# USB.net
KiCad netlist of a schematic drawn in Altium Designer
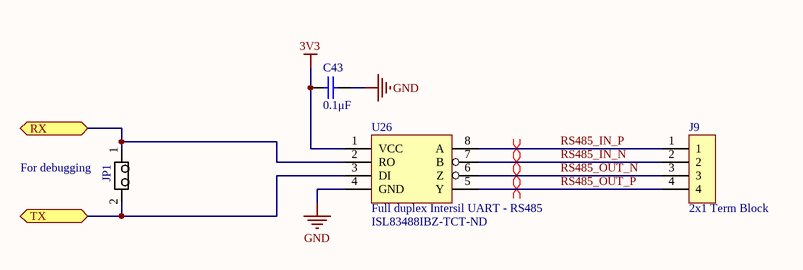
[diagram p0: USB.SchDoc]

(export (version "E")
  (design (tool "Eeschema 10.0.6"))
  (components
    (comp (ref "C43")
      (value "0.1μF")
      (footprint "CAPC1608N(0603\")")
      (description "Capacitor, Ceramic, 100V, +/- 10%, 0603 SMD, X7R")
      (fields
        (field (name "MFG") "TDK")
        (field (name "PUBLISHER") "AUVic")
        (field (name "CREATED BY") "Ashwin Sira")
      )
      (libsource (lib "AUVic_Integrated_Library_Capacitors") (part "0.1uF 100V 0603 SMD, Ceramic"))
    )
    (comp (ref "J9")
      (value "2x1 Term Block")
      (footprint "4X1 Terminal Block")
      (fields (field (name "MADE BY") "Andy Bates"))
      (libsource (lib "AUVic_Integrated_Library_Connectors") (part "4x1 Terminal Block"))
    )
    (comp (ref "JP1")
      (value "1X2 Pin Head")
      (footprint "2X1 Males Header")
      (fields (field (name "MADE BY") "Andy Bates"))
      (libsource (lib "AUVic_Schematic_Library_Connectors") (part "1x2 Male Header"))
    )
    (comp (ref "U26")
      (value "Full duplex Intersil UART - RS485")
      (footprint "SOIC-SN8_M")
      (fields
        (field (name "SUPPLIER PART NUMBER 1") "ISL83488IBZ-TCT-ND")
        (field (name "MADE BY") "Andy Bates")
      )
      (libsource (lib "AUVic_Integrated_Library_Interface") (part "Full duplex Intersil UART - RS485"))
    )
  )
  (nets
    (net (code "1") (name "/RS485_IN_N") (class "Default")
      (node (ref "J9") (pin "2") (pinfunction "2_2") (pintype "passive"))
      (node (ref "U26") (pin "7") (pinfunction "B_7") (pintype "passive"))
    )
    (net (code "2") (name "/RS485_IN_P") (class "Default")
      (node (ref "J9") (pin "1") (pinfunction "1_1") (pintype "passive"))
      (node (ref "U26") (pin "8") (pinfunction "A_8") (pintype "passive"))
    )
    (net (code "3") (name "/RS485_OUT_N") (class "Default")
      (node (ref "J9") (pin "3") (pinfunction "3_3") (pintype "passive"))
      (node (ref "U26") (pin "6") (pinfunction "Z_6") (pintype "passive"))
    )
    (net (code "4") (name "/RS485_OUT_P") (class "Default")
      (node (ref "J9") (pin "4") (pinfunction "4_4") (pintype "passive"))
      (node (ref "U26") (pin "5") (pinfunction "Y_5") (pintype "passive"))
    )
    (net (code "5") (name "/RX") (class "Default")
      (node (ref "JP1") (pin "1") (pinfunction "1_1") (pintype "passive"))
      (node (ref "U26") (pin "2") (pinfunction "RO_2") (pintype "passive"))
    )
    (net (code "6") (name "/TX") (class "Default")
      (node (ref "JP1") (pin "2") (pinfunction "2_2") (pintype "passive"))
      (node (ref "U26") (pin "3") (pinfunction "DI_3") (pintype "passive"))
    )
    (net (code "7") (name "3V3") (class "Default")
      (node (ref "C43") (pin "2") (pinfunction "Cathode_2") (pintype "passive"))
      (node (ref "U26") (pin "1") (pinfunction "VCC_1") (pintype "passive"))
    )
    (net (code "8") (name "GND") (class "Default")
      (node (ref "C43") (pin "1") (pinfunction "Anode_1") (pintype "passive"))
      (node (ref "U26") (pin "4") (pinfunction "GND_4") (pintype "passive"))
    )
  )
)
